# Microphone.net
KiCad netlist of a schematic drawn in Altium Designer
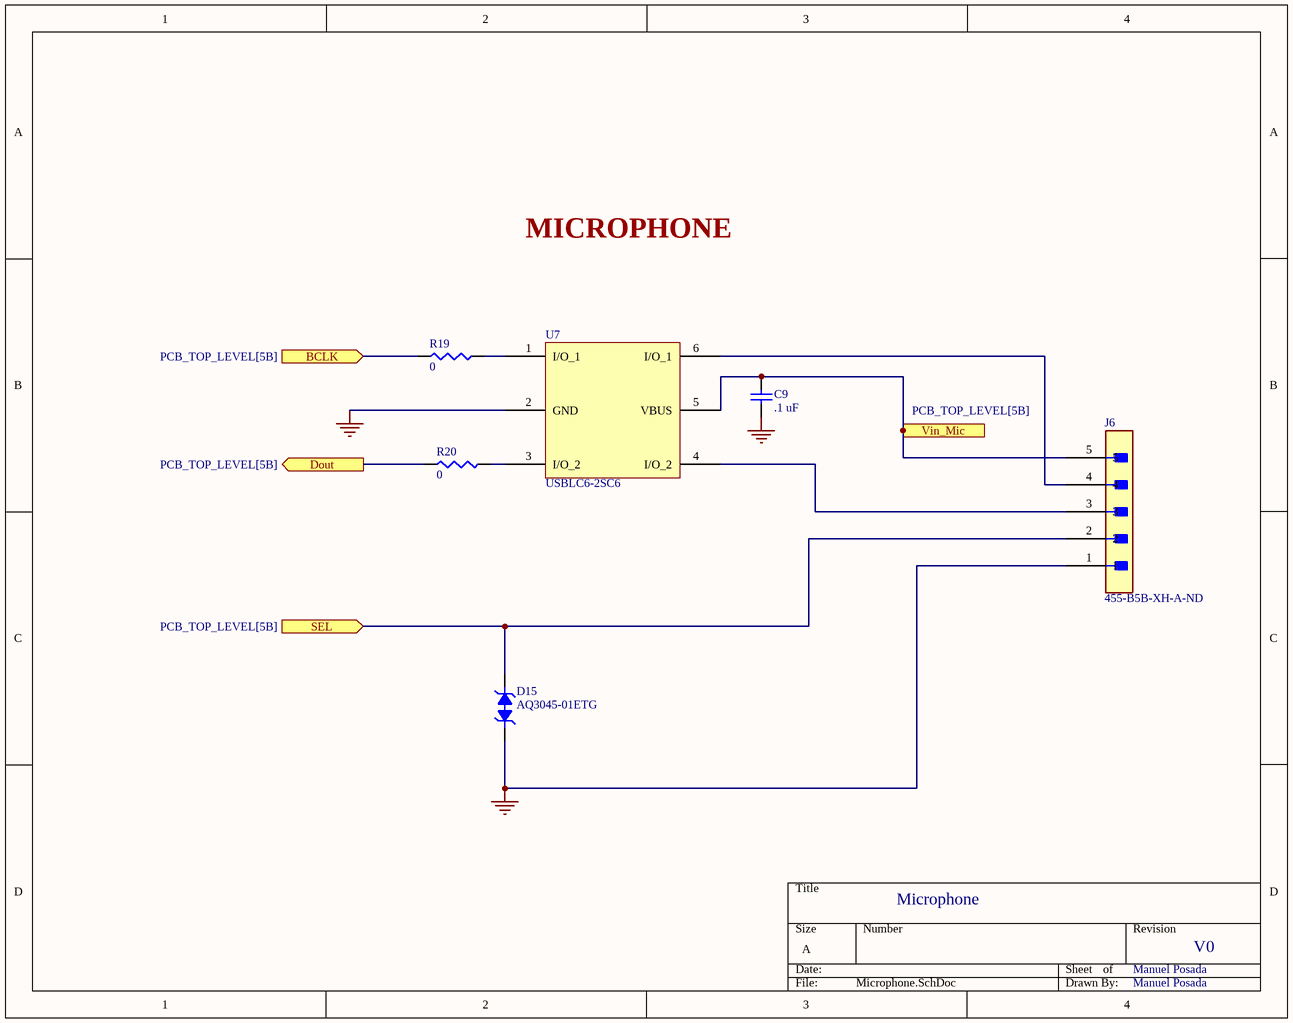
[diagram p0: Microphone.SchDoc]

(export (version "E")
  (design (tool "Eeschema 10.0.6"))
  (components
    (comp (ref "C9")
      (value ".1 uF")
      (footprint "CAP_CL21_SAM-L")
      (description "50V 100nF X7R ±10% 0805 Multilayer Ceramic Capacitors MLCC - SMD/SMT ROHS")
      (fields
        (field (name "MANUFACTURER") "Samsung Electro-Mechanics")
        (field (name "MANUFACTURER PART NUMBER") "CL21B104KBCNNNC")
      )
      (libsource (lib "Schlib") (part "CL21B104KBCNNNC"))
    )
    (comp (ref "D15")
      (value "AQ3045-01ETG")
      (footprint "SOD882")
      (description "TVS DIODE 5.3VWM 12VC SOD882")
      (fields (field (name "MANUFACTURER") "Littelfuse") (field (name "LCSC PART NUMBER") "C3710326"))
      (libsource (lib "Schlib") (part "AQ3045-01ETG"))
    )
    (comp (ref "J6")
      (value "455-B5B-XH-A-ND")
      (footprint "CONN_B5B-XH-A_JST")
      (description "Board Connector, 5 Contact(s), 1 Row(s), Male, Straight, 0.098 inch Pitch, Solder Terminal")
      (fields (field (name "MANUFACTURER") "JST") (field (name "MANUFACTURER PART NUMBER") "B5B-XH-A"))
      (libsource (lib "Schlib") (part "B5B-XH-A"))
    )
    (comp (ref "R19")
      (value "0")
      (footprint "RES_1220_SUS-L")
      (description "GENERAL PURPOSE CHIP RESISTOR Metal Glaze/thick Film, 0.125W, 0ohm, Surface Mount, 0805")
      (fields
        (field (name "MANUFACTURER") "Yageo Group")
        (field (name "MANUFACTURER PART NUMBER") "RC0805JR-070RL")
      )
      (libsource (lib "Schlib") (part "RC0805JR-070RL"))
    )
    (comp (ref "R20")
      (value "0")
      (footprint "RES_1220_SUS-L")
      (description "GENERAL PURPOSE CHIP RESISTOR Metal Glaze/thick Film, 0.125W, 0ohm, Surface Mount, 0805")
      (fields
        (field (name "MANUFACTURER") "Yageo Group")
        (field (name "MANUFACTURER PART NUMBER") "RC0805JR-070RL")
      )
      (libsource (lib "Schlib") (part "RC0805JR-070RL"))
    )
    (comp (ref "U7")
      (value "USBLC6-2SC6")
      (footprint "SOT23-6L_STM")
      (description "17V Clamp 5A (8/20µs) Ipp Tvs Diode Surface Mount SOT-23-6")
      (fields (field (name "MANUFACTURER") "STMicroelectronics"))
      (libsource (lib "Schlib") (part "USBLC6-2SC6"))
    )
  )
  (nets
    (net (code "1") (name "/BCLK") (class "Default")
      (node (ref "R19") (pin "1") (pinfunction "1_1") (pintype "passive"))
    )
    (net (code "2") (name "/Dout") (class "Default")
      (node (ref "R20") (pin "1") (pinfunction "1_1") (pintype "passive"))
    )
    (net (code "3") (name "/SEL") (class "Default")
      (node (ref "D15") (pin "2") (pinfunction "2_2") (pintype "passive"))
      (node (ref "J6") (pin "2") (pinfunction "2_2") (pintype "passive"))
    )
    (net (code "4") (name "/Vin_Mic") (class "Default")
      (node (ref "C9") (pin "2") (pinfunction "2_2") (pintype "passive"))
      (node (ref "J6") (pin "5") (pinfunction "5_5") (pintype "passive"))
      (node (ref "U7") (pin "5") (pinfunction "VBUS_5") (pintype "passive"))
    )
    (net (code "5") (name "GND") (class "Default")
      (node (ref "C9") (pin "1") (pinfunction "1_1") (pintype "passive"))
      (node (ref "D15") (pin "1") (pinfunction "1_1") (pintype "passive"))
      (node (ref "J6") (pin "1") (pinfunction "1_1") (pintype "passive"))
      (node (ref "U7") (pin "2") (pinfunction "GND_2") (pintype "passive"))
    )
    (net (code "6") (name "Net-(J6-Pad3)") (class "Default")
      (node (ref "J6") (pin "3") (pinfunction "3_3") (pintype "passive"))
      (node (ref "U7") (pin "4") (pinfunction "I/O_2_4") (pintype "passive"))
    )
    (net (code "7") (name "Net-(J6-Pad4)") (class "Default")
      (node (ref "J6") (pin "4") (pinfunction "4_4") (pintype "passive"))
      (node (ref "U7") (pin "6") (pinfunction "I/O_1_6") (pintype "passive"))
    )
    (net (code "8") (name "Net-(R19-Pad2)") (class "Default")
      (node (ref "R19") (pin "2") (pinfunction "2_2") (pintype "passive"))
      (node (ref "U7") (pin "1") (pinfunction "I/O_1_1") (pintype "passive"))
    )
    (net (code "9") (name "Net-(R20-Pad2)") (class "Default")
      (node (ref "R20") (pin "2") (pinfunction "2_2") (pintype "passive"))
      (node (ref "U7") (pin "3") (pinfunction "I/O_2_3") (pintype "passive"))
    )
  )
)
